# Main.net
KiCad netlist of a schematic drawn in Altium Designer
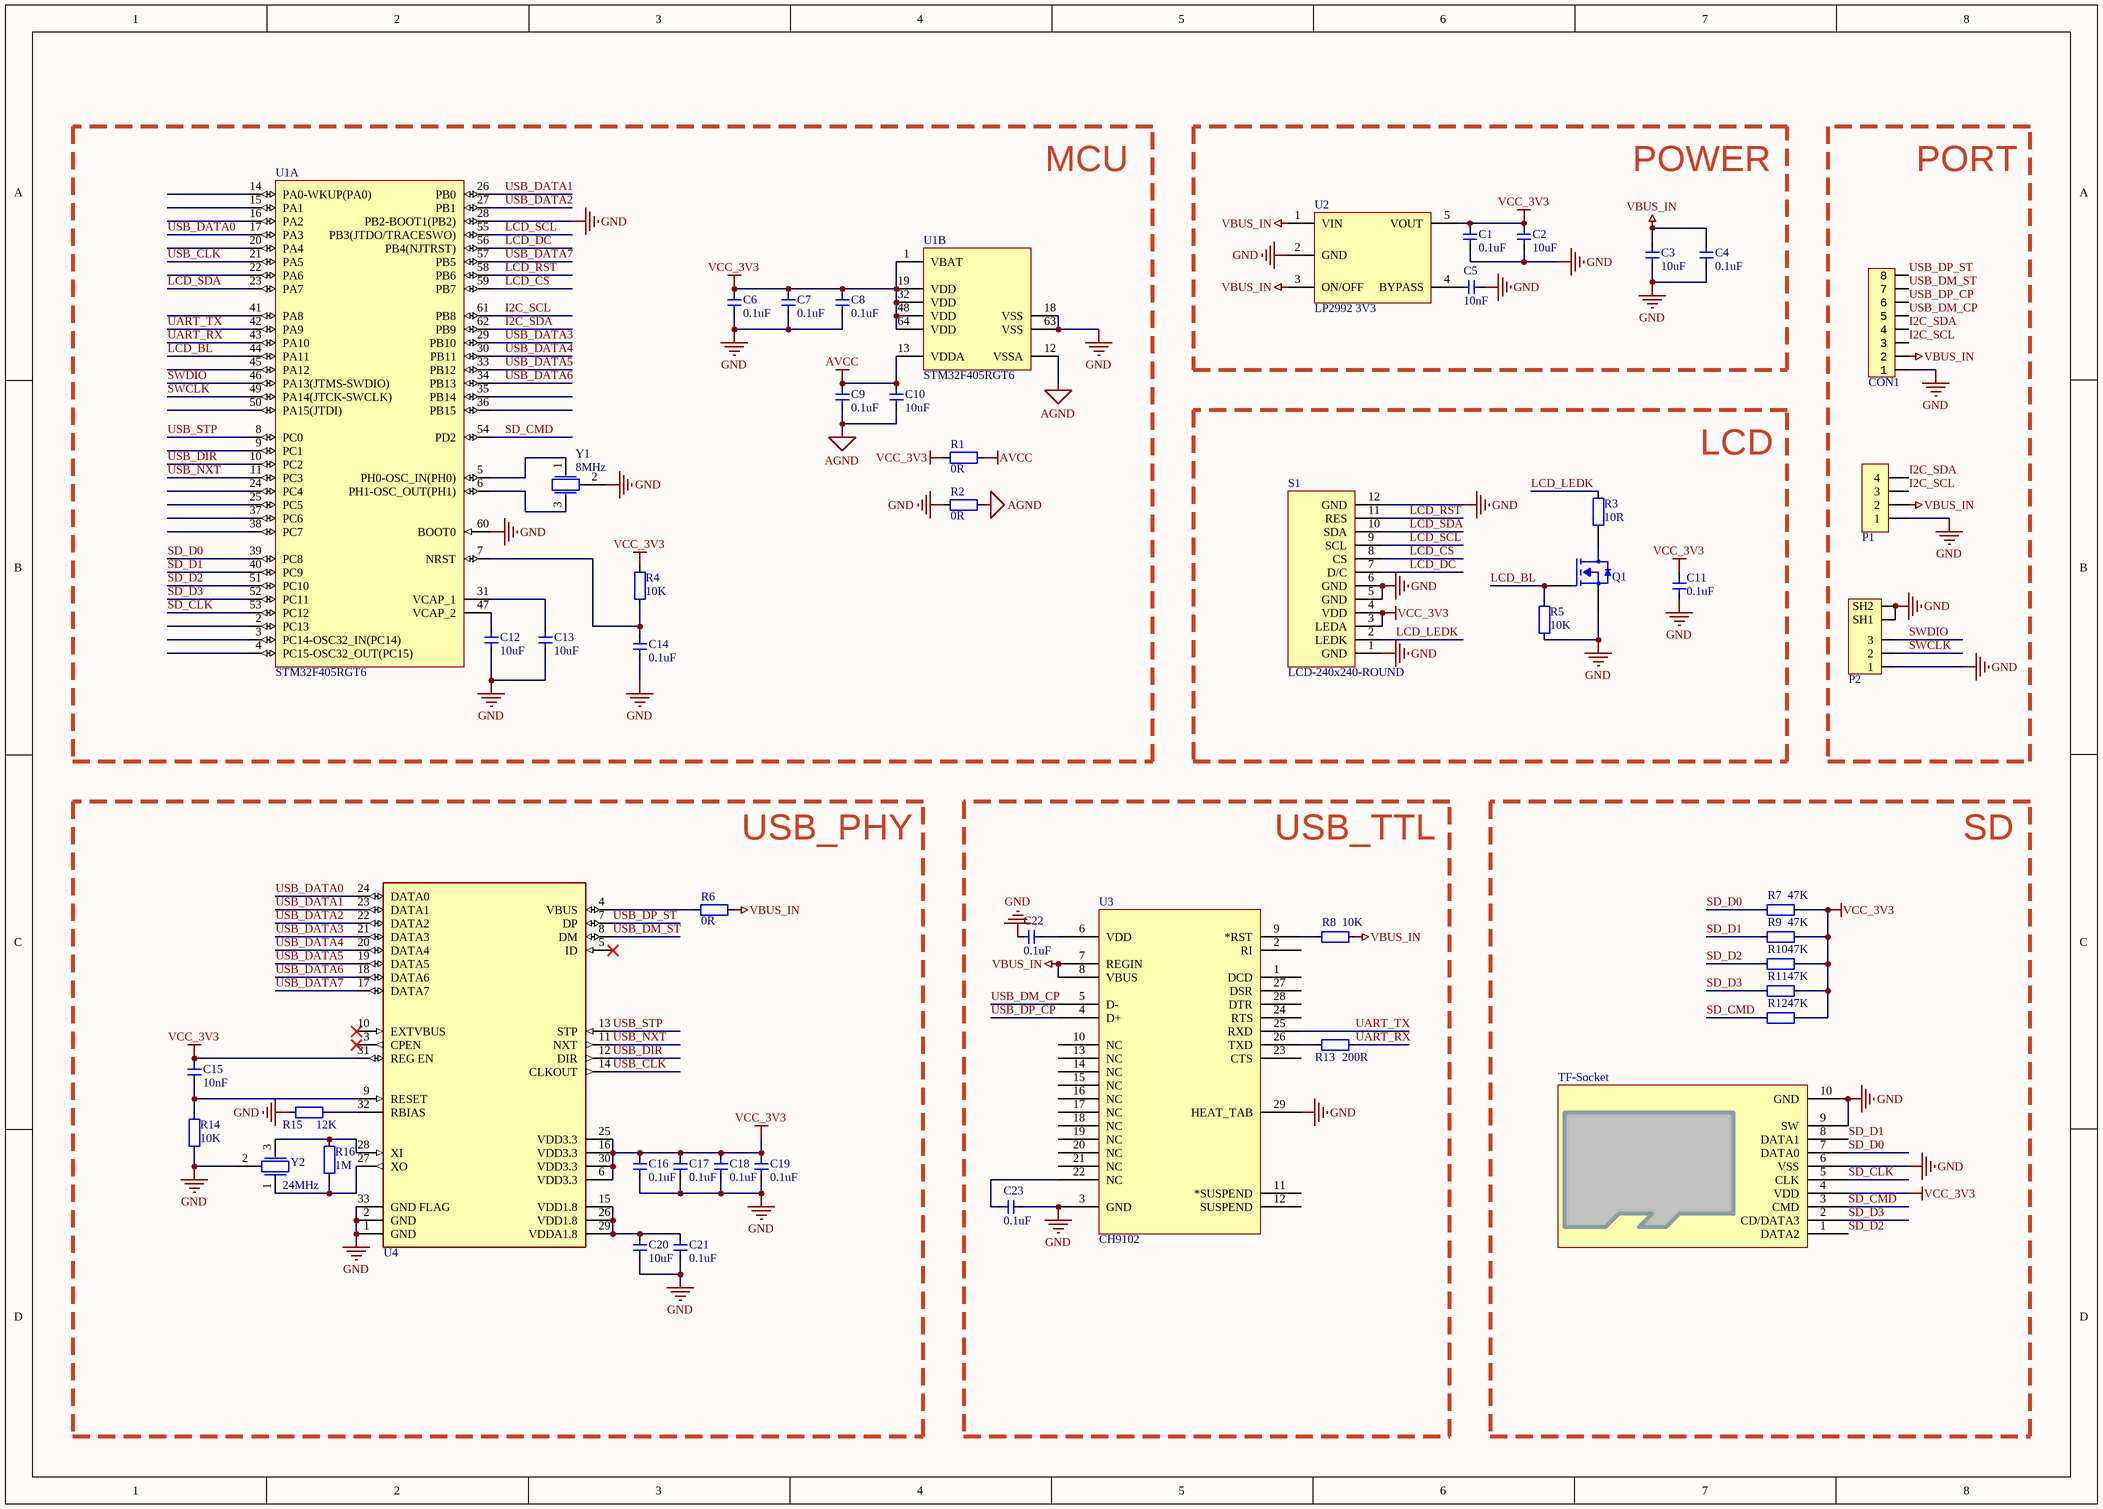
[diagram p0: Main.SchDoc]

(export (version "E")
  (design (tool "Eeschema 10.0.6"))
  (components
    (comp (ref "C1")
      (value "0.1uF")
      (footprint "ElectronBot:CAP_0402")
      (description "Capacitor")
      (libsource (lib "MyPcbLib") (part "电容-0402"))
    )
    (comp (ref "C2")
      (value "10uF")
      (footprint "ElectronBot:CAP_0402")
      (description "Capacitor")
      (libsource (lib "MyPcbLib") (part "电容-0402"))
    )
    (comp (ref "C3")
      (value "10uF")
      (footprint "ElectronBot:CAP_0402")
      (description "Capacitor")
      (libsource (lib "MyPcbLib") (part "电容-0402"))
    )
    (comp (ref "C4")
      (value "0.1uF")
      (footprint "ElectronBot:CAP_0402")
      (description "Capacitor")
      (libsource (lib "MyPcbLib") (part "电容-0402"))
    )
    (comp (ref "C5")
      (value "10nF")
      (footprint "ElectronBot:CAP_0402")
      (description "Capacitor")
      (libsource (lib "MyPcbLib") (part "电容-0402"))
    )
    (comp (ref "C6")
      (value "0.1uF")
      (footprint "ElectronBot:CAP_0402")
      (description "Capacitor")
      (libsource (lib "MyPcbLib") (part "电容-0402"))
    )
    (comp (ref "C7")
      (value "0.1uF")
      (footprint "ElectronBot:CAP_0402")
      (description "Capacitor")
      (libsource (lib "MyPcbLib") (part "电容-0402"))
    )
    (comp (ref "C8")
      (value "0.1uF")
      (footprint "ElectronBot:CAP_0402")
      (description "Capacitor")
      (libsource (lib "MyPcbLib") (part "电容-0402"))
    )
    (comp (ref "C9")
      (value "0.1uF")
      (footprint "ElectronBot:CAP_0402")
      (description "Capacitor")
      (libsource (lib "MyPcbLib") (part "电容-0402"))
    )
    (comp (ref "C10")
      (value "10uF")
      (footprint "ElectronBot:CAP_0402")
      (description "Capacitor")
      (libsource (lib "MyPcbLib") (part "电容-0402"))
    )
    (comp (ref "C11")
      (value "0.1uF")
      (footprint "ElectronBot:CAP_0402")
      (description "Capacitor")
      (libsource (lib "MyPcbLib") (part "电容-0402"))
    )
    (comp (ref "C12")
      (value "10uF")
      (footprint "ElectronBot:CAP_0402")
      (description "Capacitor")
      (libsource (lib "MyPcbLib") (part "电容-0402"))
    )
    (comp (ref "C13")
      (value "10uF")
      (footprint "ElectronBot:CAP_0402")
      (description "Capacitor")
      (libsource (lib "MyPcbLib") (part "电容-0402"))
    )
    (comp (ref "C14")
      (value "0.1uF")
      (footprint "ElectronBot:CAP_0402")
      (description "Capacitor")
      (libsource (lib "MyPcbLib") (part "电容-0402"))
    )
    (comp (ref "C15")
      (value "10nF")
      (footprint "ElectronBot:CAP_0402")
      (description "Capacitor")
      (libsource (lib "MyPcbLib") (part "电容-0402"))
    )
    (comp (ref "C16")
      (value "0.1uF")
      (footprint "ElectronBot:CAP_0402")
      (description "Capacitor")
      (libsource (lib "MyPcbLib") (part "电容-0402"))
    )
    (comp (ref "C17")
      (value "0.1uF")
      (footprint "ElectronBot:CAP_0402")
      (description "Capacitor")
      (libsource (lib "MyPcbLib") (part "电容-0402"))
    )
    (comp (ref "C18")
      (value "0.1uF")
      (footprint "ElectronBot:CAP_0402")
      (description "Capacitor")
      (libsource (lib "MyPcbLib") (part "电容-0402"))
    )
    (comp (ref "C19")
      (value "0.1uF")
      (footprint "ElectronBot:CAP_0402")
      (description "Capacitor")
      (libsource (lib "MyPcbLib") (part "电容-0402"))
    )
    (comp (ref "C20")
      (value "10uF")
      (footprint "ElectronBot:CAP_0402")
      (description "Capacitor")
      (libsource (lib "MyPcbLib") (part "电容-0402"))
    )
    (comp (ref "C21")
      (value "0.1uF")
      (footprint "ElectronBot:CAP_0402")
      (description "Capacitor")
      (libsource (lib "MyPcbLib") (part "电容-0402"))
    )
    (comp (ref "C22")
      (value "0.1uF")
      (footprint "ElectronBot:CAP_0402")
      (description "Capacitor")
      (libsource (lib "MyPcbLib") (part "电容-0402"))
    )
    (comp (ref "C23")
      (value "0.1uF")
      (footprint "ElectronBot:CAP_0402")
      (description "Capacitor")
      (libsource (lib "MyPcbLib") (part "电容-0402"))
    )
    (comp (ref "CON1")
      (value "FFC_0.5_8")
      (footprint "ElectronBot:FFC_0.5_8")
      (description "FFC")
      (libsource (lib "KitSprout") (part "FFC_0.5_8"))
    )
    (comp (ref "P1")
      (value "CON-4P")
      (footprint "ElectronBot:SH1.0-4P")
      (description "4P连接器")
      (libsource (lib "4.9 - 0.5mm连接器(FPC0.5)") (part "Header 4"))
    )
    (comp (ref "P2")
      (value "SH1.0-3P-STAND")
      (footprint "ElectronBot:SH1.0-3P-STAND")
      (description "Header")
      (libsource (lib "MyPcbLib") (part "SH1.0-3P-STAND"))
    )
    (comp (ref "Q1")
      (value "AO3400A")
      (footprint "ElectronBot:SOT23-3")
      (description "N-MOS")
      (libsource (lib "MyPcbLib") (part "AO3400A"))
    )
    (comp (ref "R1")
      (value "0R")
      (footprint "ElectronBot:RES_0402")
      (description "Resistor")
      (libsource (lib "") (part "电阻-0402_1"))
    )
    (comp (ref "R2")
      (value "0R")
      (footprint "ElectronBot:RES_0402")
      (description "Resistor")
      (libsource (lib "") (part "电阻-0402_1"))
    )
    (comp (ref "R3")
      (value "10R")
      (footprint "ElectronBot:RES_0402")
      (description "Resistor")
      (libsource (lib "MyPcbLib") (part "电阻-0402"))
    )
    (comp (ref "R4")
      (value "10K")
      (footprint "ElectronBot:RES_0402")
      (description "Resistor")
      (libsource (lib "MyPcbLib") (part "电阻-0402"))
    )
    (comp (ref "R5")
      (value "10K")
      (footprint "ElectronBot:RES_0402")
      (description "Resistor")
      (libsource (lib "MyPcbLib") (part "电阻-0402"))
    )
    (comp (ref "R6")
      (value "0R")
      (footprint "ElectronBot:RES_0402")
      (description "Resistor")
      (libsource (lib "") (part "电阻-0402_1"))
    )
    (comp (ref "R7")
      (value "47K")
      (footprint "ElectronBot:RES_0402")
      (description "Resistor")
      (libsource (lib "") (part "电阻-0402_1"))
    )
    (comp (ref "R8")
      (value "10K")
      (footprint "ElectronBot:RES_0402")
      (description "Resistor")
      (libsource (lib "") (part "电阻-0402_1"))
    )
    (comp (ref "R9")
      (value "47K")
      (footprint "ElectronBot:RES_0402")
      (description "Resistor")
      (libsource (lib "") (part "电阻-0402_1"))
    )
    (comp (ref "R10")
      (value "47K")
      (footprint "ElectronBot:RES_0402")
      (description "Resistor")
      (libsource (lib "") (part "电阻-0402_1"))
    )
    (comp (ref "R11")
      (value "47K")
      (footprint "ElectronBot:RES_0402")
      (description "Resistor")
      (libsource (lib "") (part "电阻-0402_1"))
    )
    (comp (ref "R12")
      (value "47K")
      (footprint "ElectronBot:RES_0402")
      (description "Resistor")
      (libsource (lib "") (part "电阻-0402_1"))
    )
    (comp (ref "R13")
      (value "200R")
      (footprint "ElectronBot:RES_0402")
      (description "Resistor")
      (libsource (lib "") (part "电阻-0402_1"))
    )
    (comp (ref "R14")
      (value "10K")
      (footprint "ElectronBot:RES_0402")
      (description "Resistor")
      (libsource (lib "") (part "电阻-0402_2"))
    )
    (comp (ref "R15")
      (value "12K")
      (footprint "ElectronBot:RES_0402")
      (description "Resistor")
      (libsource (lib "") (part "电阻-0402_1"))
    )
    (comp (ref "R16")
      (value "1M")
      (footprint "ElectronBot:RES_0402")
      (description "Resistor")
      (libsource (lib "") (part "电阻-0402_2"))
    )
    (comp (ref "S1")
      (value "LCD-240x240-ROUND")
      (footprint "ElectronBot:LCD-240x240-ROUND")
      (description "显示屏")
      (libsource (lib "mLib") (part "LCD-240x240-ROUND"))
    )
    (comp (ref "TF-Socket")
      (value "TF")
      (footprint "ElectronBot:TF-Card-Amphenol with TF")
      (description "8脚自弹")
      (libsource (lib "MyPcbLib") (part "TF卡座"))
    )
    (comp (ref "U1")
      (value "STM32F405RGT6")
      (footprint "ElectronBot:LQFP-64_N")
      (fields (field (name "MANUFACTURER") "STMicroelectronics"))
      (libsource (lib "STMicroelectronics STM32 F4") (part "STM32F405RGT6"))
    )
    (comp (ref "U2")
      (value "LP2992 3V3")
      (footprint "ElectronBot:SOT23-5")
      (description "LDO")
      (libsource (lib "MyPcbLib") (part "LP2992"))
    )
    (comp (ref "U3")
      (value "CH9102")
      (footprint "ElectronBot:QFN-28")
      (description "USB转TTL")
      (fields (field (name "PART NUMBER") "CP2102"))
      (libsource (lib "mLib") (part "CP2102"))
    )
    (comp (ref "U4")
      (value "USB3300-EZK-TR")
      (footprint "ElectronBot:QFN-32")
      (libsource (lib "mLib") (part "USB3300-EZK-TR"))
    )
    (comp (ref "Y1")
      (value "8MHz")
      (footprint "ElectronBot:晶振-3P")
      (description "村田贴片")
      (libsource (lib "MyPcbLib") (part "晶振-3Pin"))
    )
    (comp (ref "Y2")
      (value "24MHz")
      (footprint "ElectronBot:晶振-3P")
      (description "村田贴片")
      (libsource (lib "MyPcbLib") (part "晶振-3Pin"))
    )
  )
  (nets
    (net (code "1") (name "/I2C_SCL") (class "Default")
      (node (ref "CON1") (pin "3") (pinfunction "3_3") (pintype "passive"))
      (node (ref "P1") (pin "3") (pinfunction "3_3") (pintype "passive"))
      (node (ref "U1") (pin "61") (pinfunction "PB8_61") (pintype "bidirectional"))
    )
    (net (code "2") (name "/I2C_SDA") (class "Default")
      (node (ref "CON1") (pin "4") (pinfunction "4_4") (pintype "passive"))
      (node (ref "P1") (pin "4") (pinfunction "4_4") (pintype "passive"))
      (node (ref "U1") (pin "62") (pinfunction "PB9_62") (pintype "bidirectional"))
    )
    (net (code "3") (name "/LCD_BL") (class "Default")
      (node (ref "Q1") (pin "1") (pinfunction "G_1") (pintype "passive"))
      (node (ref "R5") (pin "2") (pinfunction "2_2") (pintype "passive"))
      (node (ref "U1") (pin "44") (pinfunction "PA11_44") (pintype "bidirectional"))
    )
    (net (code "4") (name "/LCD_CS") (class "Default")
      (node (ref "S1") (pin "8") (pinfunction "CS_8") (pintype "passive"))
      (node (ref "U1") (pin "59") (pinfunction "PB7_59") (pintype "bidirectional"))
    )
    (net (code "5") (name "/LCD_DC") (class "Default")
      (node (ref "S1") (pin "7") (pinfunction "D/C_7") (pintype "passive"))
      (node (ref "U1") (pin "56") (pinfunction "PB4(NJTRST)_56") (pintype "bidirectional"))
    )
    (net (code "6") (name "/LCD_LEDK") (class "Default")
      (node (ref "R3") (pin "2") (pinfunction "2_2") (pintype "passive"))
      (node (ref "S1") (pin "2") (pinfunction "LEDK_2") (pintype "passive"))
    )
    (net (code "7") (name "/LCD_RST") (class "Default")
      (node (ref "S1") (pin "11") (pinfunction "RES_11") (pintype "passive"))
      (node (ref "U1") (pin "58") (pinfunction "PB6_58") (pintype "bidirectional"))
    )
    (net (code "8") (name "/LCD_SCL") (class "Default")
      (node (ref "S1") (pin "9") (pinfunction "SCL_9") (pintype "passive"))
      (node (ref "U1") (pin "55") (pinfunction "PB3(JTDO/TRACESWO)_55") (pintype "bidirectional"))
    )
    (net (code "9") (name "/LCD_SDA") (class "Default")
      (node (ref "S1") (pin "10") (pinfunction "SDA_10") (pintype "passive"))
      (node (ref "U1") (pin "23") (pinfunction "PA7_23") (pintype "bidirectional"))
    )
    (net (code "10") (name "/SD_CLK") (class "Default")
      (node (ref "TF-Socket") (pin "5") (pinfunction "CLK_5") (pintype "passive"))
      (node (ref "U1") (pin "53") (pinfunction "PC12_53") (pintype "bidirectional"))
    )
    (net (code "11") (name "/SD_CMD") (class "Default")
      (node (ref "R12") (pin "2") (pinfunction "2_2") (pintype "passive"))
      (node (ref "TF-Socket") (pin "3") (pinfunction "CMD_3") (pintype "passive"))
      (node (ref "U1") (pin "54") (pinfunction "PD2_54") (pintype "bidirectional"))
    )
    (net (code "12") (name "/SD_D0") (class "Default")
      (node (ref "R7") (pin "2") (pinfunction "2_2") (pintype "passive"))
      (node (ref "TF-Socket") (pin "7") (pinfunction "DATA0_7") (pintype "passive"))
      (node (ref "U1") (pin "39") (pinfunction "PC8_39") (pintype "bidirectional"))
    )
    (net (code "13") (name "/SD_D1") (class "Default")
      (node (ref "R9") (pin "2") (pinfunction "2_2") (pintype "passive"))
      (node (ref "TF-Socket") (pin "8") (pinfunction "DATA1_8") (pintype "passive"))
      (node (ref "U1") (pin "40") (pinfunction "PC9_40") (pintype "bidirectional"))
    )
    (net (code "14") (name "/SD_D2") (class "Default")
      (node (ref "R10") (pin "2") (pinfunction "2_2") (pintype "passive"))
      (node (ref "TF-Socket") (pin "1") (pinfunction "DATA2_1") (pintype "passive"))
      (node (ref "U1") (pin "51") (pinfunction "PC10_51") (pintype "bidirectional"))
    )
    (net (code "15") (name "/SD_D3") (class "Default")
      (node (ref "R11") (pin "2") (pinfunction "2_2") (pintype "passive"))
      (node (ref "TF-Socket") (pin "2") (pinfunction "CD/DATA3_2") (pintype "passive"))
      (node (ref "U1") (pin "52") (pinfunction "PC11_52") (pintype "bidirectional"))
    )
    (net (code "16") (name "/SWCLK") (class "Default")
      (node (ref "P2") (pin "2") (pinfunction "2_2") (pintype "passive"))
      (node (ref "U1") (pin "49") (pinfunction "PA14(JTCK-SWCLK)_49") (pintype "bidirectional"))
    )
    (net (code "17") (name "/SWDIO") (class "Default")
      (node (ref "P2") (pin "3") (pinfunction "3_3") (pintype "passive"))
      (node (ref "U1") (pin "46") (pinfunction "PA13(JTMS-SWDIO)_46") (pintype "bidirectional"))
    )
    (net (code "18") (name "/UART_RX") (class "Default")
      (node (ref "R13") (pin "1") (pinfunction "1_1") (pintype "passive"))
      (node (ref "U1") (pin "43") (pinfunction "PA10_43") (pintype "bidirectional"))
    )
    (net (code "19") (name "/UART_TX") (class "Default")
      (node (ref "U1") (pin "42") (pinfunction "PA9_42") (pintype "bidirectional"))
      (node (ref "U3") (pin "25") (pinfunction "RXD_25") (pintype "passive"))
    )
    (net (code "20") (name "/USB_CLK") (class "Default")
      (node (ref "U1") (pin "21") (pinfunction "PA5_21") (pintype "bidirectional"))
      (node (ref "U4") (pin "14") (pinfunction "CLKOUT_14") (pintype "output"))
    )
    (net (code "21") (name "/USB_DATA0") (class "Default")
      (node (ref "U1") (pin "17") (pinfunction "PA3_17") (pintype "bidirectional"))
      (node (ref "U4") (pin "24") (pinfunction "DATA0_24") (pintype "bidirectional"))
    )
    (net (code "22") (name "/USB_DATA1") (class "Default")
      (node (ref "U1") (pin "26") (pinfunction "PB0_26") (pintype "bidirectional"))
      (node (ref "U4") (pin "23") (pinfunction "DATA1_23") (pintype "bidirectional"))
    )
    (net (code "23") (name "/USB_DATA2") (class "Default")
      (node (ref "U1") (pin "27") (pinfunction "PB1_27") (pintype "bidirectional"))
      (node (ref "U4") (pin "22") (pinfunction "DATA2_22") (pintype "bidirectional"))
    )
    (net (code "24") (name "/USB_DATA3") (class "Default")
      (node (ref "U1") (pin "29") (pinfunction "PB10_29") (pintype "bidirectional"))
      (node (ref "U4") (pin "21") (pinfunction "DATA3_21") (pintype "bidirectional"))
    )
    (net (code "25") (name "/USB_DATA4") (class "Default")
      (node (ref "U1") (pin "30") (pinfunction "PB11_30") (pintype "bidirectional"))
      (node (ref "U4") (pin "20") (pinfunction "DATA4_20") (pintype "bidirectional"))
    )
    (net (code "26") (name "/USB_DATA5") (class "Default")
      (node (ref "U1") (pin "33") (pinfunction "PB12_33") (pintype "bidirectional"))
      (node (ref "U4") (pin "19") (pinfunction "DATA5_19") (pintype "bidirectional"))
    )
    (net (code "27") (name "/USB_DATA6") (class "Default")
      (node (ref "U1") (pin "34") (pinfunction "PB13_34") (pintype "bidirectional"))
      (node (ref "U4") (pin "18") (pinfunction "DATA6_18") (pintype "bidirectional"))
    )
    (net (code "28") (name "/USB_DATA7") (class "Default")
      (node (ref "U1") (pin "57") (pinfunction "PB5_57") (pintype "bidirectional"))
      (node (ref "U4") (pin "17") (pinfunction "DATA7_17") (pintype "bidirectional"))
    )
    (net (code "29") (name "/USB_DIR") (class "Default")
      (node (ref "U1") (pin "10") (pinfunction "PC2_10") (pintype "bidirectional"))
      (node (ref "U4") (pin "12") (pinfunction "DIR_12") (pintype "output"))
    )
    (net (code "30") (name "/USB_DM_CP") (class "Default")
      (node (ref "CON1") (pin "5") (pinfunction "5_5") (pintype "passive"))
      (node (ref "U3") (pin "5") (pinfunction "D-_5") (pintype "passive"))
    )
    (net (code "31") (name "/USB_DM_ST") (class "Default")
      (node (ref "CON1") (pin "7") (pinfunction "7_7") (pintype "passive"))
      (node (ref "U4") (pin "8") (pinfunction "DM_8") (pintype "bidirectional"))
    )
    (net (code "32") (name "/USB_DP_CP") (class "Default")
      (node (ref "CON1") (pin "6") (pinfunction "6_6") (pintype "passive"))
      (node (ref "U3") (pin "4") (pinfunction "D+_4") (pintype "passive"))
    )
    (net (code "33") (name "/USB_DP_ST") (class "Default")
      (node (ref "CON1") (pin "8") (pinfunction "8_8") (pintype "passive"))
      (node (ref "U4") (pin "7") (pinfunction "DP_7") (pintype "bidirectional"))
    )
    (net (code "34") (name "/USB_NXT") (class "Default")
      (node (ref "U1") (pin "11") (pinfunction "PC3_11") (pintype "bidirectional"))
      (node (ref "U4") (pin "11") (pinfunction "NXT_11") (pintype "output"))
    )
    (net (code "35") (name "/USB_STP") (class "Default")
      (node (ref "U1") (pin "8") (pinfunction "PC0_8") (pintype "bidirectional"))
      (node (ref "U4") (pin "13") (pinfunction "STP_13") (pintype "input"))
    )
    (net (code "36") (name "AGND") (class "Default")
      (node (ref "C10") (pin "1") (pinfunction "1_1") (pintype "passive"))
      (node (ref "C9") (pin "1") (pinfunction "1_1") (pintype "passive"))
      (node (ref "R2") (pin "1") (pinfunction "1_1") (pintype "passive"))
      (node (ref "U1") (pin "12") (pinfunction "VSSA_12") (pintype "power_in"))
    )
    (net (code "37") (name "AVCC") (class "Default")
      (node (ref "C10") (pin "2") (pinfunction "2_2") (pintype "passive"))
      (node (ref "C9") (pin "2") (pinfunction "2_2") (pintype "passive"))
      (node (ref "R1") (pin "1") (pinfunction "1_1") (pintype "passive"))
      (node (ref "U1") (pin "13") (pinfunction "VDDA_13") (pintype "power_in"))
    )
    (net (code "38") (name "GND") (class "Default")
      (node (ref "C1") (pin "1") (pinfunction "1_1") (pintype "passive"))
      (node (ref "C11") (pin "1") (pinfunction "1_1") (pintype "passive"))
      (node (ref "C12") (pin "1") (pinfunction "1_1") (pintype "passive"))
      (node (ref "C13") (pin "1") (pinfunction "1_1") (pintype "passive"))
      (node (ref "C14") (pin "1") (pinfunction "1_1") (pintype "passive"))
      (node (ref "C16") (pin "2") (pinfunction "2_2") (pintype "passive"))
      (node (ref "C17") (pin "2") (pinfunction "2_2") (pintype "passive"))
      (node (ref "C18") (pin "2") (pinfunction "2_2") (pintype "passive"))
      (node (ref "C19") (pin "2") (pinfunction "2_2") (pintype "passive"))
      (node (ref "C2") (pin "1") (pinfunction "1_1") (pintype "passive"))
      (node (ref "C20") (pin "2") (pinfunction "2_2") (pintype "passive"))
      (node (ref "C21") (pin "2") (pinfunction "2_2") (pintype "passive"))
      (node (ref "C22") (pin "2") (pinfunction "2_2") (pintype "passive"))
      (node (ref "C23") (pin "1") (pinfunction "1_1") (pintype "passive"))
      (node (ref "C3") (pin "1") (pinfunction "1_1") (pintype "passive"))
      (node (ref "C4") (pin "1") (pinfunction "1_1") (pintype "passive"))
      (node (ref "C5") (pin "1") (pinfunction "1_1") (pintype "passive"))
      (node (ref "C6") (pin "1") (pinfunction "1_1") (pintype "passive"))
      (node (ref "C7") (pin "1") (pinfunction "1_1") (pintype "passive"))
      (node (ref "C8") (pin "1") (pinfunction "1_1") (pintype "passive"))
      (node (ref "CON1") (pin "1") (pinfunction "1_1") (pintype "passive"))
      (node (ref "P1") (pin "1") (pinfunction "1_1") (pintype "passive"))
      (node (ref "P2") (pin "1") (pinfunction "1_1") (pintype "passive"))
      (node (ref "P2") (pin "SH1") (pinfunction "SH1_SH1") (pintype "passive"))
      (node (ref "P2") (pin "SH2") (pinfunction "SH2_SH2") (pintype "passive"))
      (node (ref "Q1") (pin "2") (pinfunction "S_2") (pintype "passive"))
      (node (ref "R14") (pin "2") (pinfunction "2_2") (pintype "passive"))
      (node (ref "R15") (pin "2") (pinfunction "2_2") (pintype "passive"))
      (node (ref "R2") (pin "2") (pinfunction "2_2") (pintype "passive"))
      (node (ref "R5") (pin "1") (pinfunction "1_1") (pintype "passive"))
      (node (ref "S1") (pin "1") (pinfunction "GND_1") (pintype "passive"))
      (node (ref "S1") (pin "12") (pinfunction "GND_12") (pintype "passive"))
      (node (ref "S1") (pin "5") (pinfunction "GND_5") (pintype "passive"))
      (node (ref "S1") (pin "6") (pinfunction "GND_6") (pintype "passive"))
      (node (ref "TF-Socket") (pin "10") (pinfunction "GND_10") (pintype "passive"))
      (node (ref "TF-Socket") (pin "6") (pinfunction "VSS_6") (pintype "passive"))
      (node (ref "TF-Socket") (pin "9") (pinfunction "SW_9") (pintype "passive"))
      (node (ref "U1") (pin "18") (pinfunction "VSS_18") (pintype "power_in"))
      (node (ref "U1") (pin "28") (pinfunction "PB2-BOOT1(PB2)_28") (pintype "bidirectional"))
      (node (ref "U1") (pin "60") (pinfunction "BOOT0_60") (pintype "input"))
      (node (ref "U1") (pin "63") (pinfunction "VSS_63") (pintype "power_in"))
      (node (ref "U2") (pin "2") (pinfunction "GND_2") (pintype "passive"))
      (node (ref "U3") (pin "29") (pinfunction "HEAT_TAB_29") (pintype "passive"))
      (node (ref "U3") (pin "3") (pinfunction "GND_3") (pintype "passive"))
      (node (ref "U4") (pin "1") (pinfunction "GND_1") (pintype "power_in"))
      (node (ref "U4") (pin "2") (pinfunction "GND_2") (pintype "power_in"))
      (node (ref "U4") (pin "33") (pinfunction "GND_FLAG_33") (pintype "power_in"))
      (node (ref "Y1") (pin "2") (pinfunction "2_2") (pintype "passive"))
      (node (ref "Y2") (pin "2") (pinfunction "2_2") (pintype "passive"))
    )
    (net (code "39") (name "Net-(C23-Pad2)") (class "Default")
      (node (ref "C23") (pin "2") (pinfunction "2_2") (pintype "passive"))
      (node (ref "U3") (pin "22") (pinfunction "NC_22") (pintype "passive"))
    )
    (net (code "40") (name "Net-(Q1-D)") (class "Default")
      (node (ref "Q1") (pin "3") (pinfunction "D_3") (pintype "passive"))
      (node (ref "R3") (pin "1") (pinfunction "1_1") (pintype "passive"))
    )
    (net (code "41") (name "Net-(U1A-NRST)") (class "Default")
      (node (ref "C14") (pin "2") (pinfunction "2_2") (pintype "passive"))
      (node (ref "R4") (pin "1") (pinfunction "1_1") (pintype "passive"))
      (node (ref "U1") (pin "7") (pinfunction "NRST_7") (pintype "bidirectional"))
    )
    (net (code "42") (name "Net-(U1A-PH0-OSC_IN(PH0))") (class "Default")
      (node (ref "U1") (pin "5") (pinfunction "PH0-OSC_IN(PH0)_5") (pintype "bidirectional"))
      (node (ref "Y1") (pin "1") (pinfunction "1_1") (pintype "passive"))
    )
    (net (code "43") (name "Net-(U1A-PH1-OSC_OUT(PH1))") (class "Default")
      (node (ref "U1") (pin "6") (pinfunction "PH1-OSC_OUT(PH1)_6") (pintype "bidirectional"))
      (node (ref "Y1") (pin "3") (pinfunction "3_3") (pintype "passive"))
    )
    (net (code "44") (name "Net-(U1A-VCAP_1)") (class "Default")
      (node (ref "C13") (pin "2") (pinfunction "2_2") (pintype "passive"))
      (node (ref "U1") (pin "31") (pinfunction "VCAP_1_31") (pintype "power_in"))
    )
    (net (code "45") (name "Net-(U1A-VCAP_2)") (class "Default")
      (node (ref "C12") (pin "2") (pinfunction "2_2") (pintype "passive"))
      (node (ref "U1") (pin "47") (pinfunction "VCAP_2_47") (pintype "power_in"))
    )
    (net (code "46") (name "Net-(U2-BYPASS)") (class "Default")
      (node (ref "C5") (pin "2") (pinfunction "2_2") (pintype "passive"))
      (node (ref "U2") (pin "4") (pinfunction "BYPASS_4") (pintype "passive"))
    )
    (net (code "47") (name "Net-(U3-*RST)") (class "Default")
      (node (ref "R8") (pin "2") (pinfunction "2_2") (pintype "passive"))
      (node (ref "U3") (pin "9") (pinfunction "*RST_9") (pintype "passive"))
    )
    (net (code "48") (name "Net-(U3-TXD)") (class "Default")
      (node (ref "R13") (pin "2") (pinfunction "2_2") (pintype "passive"))
      (node (ref "U3") (pin "26") (pinfunction "TXD_26") (pintype "passive"))
    )
    (net (code "49") (name "Net-(U3-VDD)") (class "Default")
      (node (ref "C22") (pin "1") (pinfunction "1_1") (pintype "passive"))
      (node (ref "U3") (pin "6") (pinfunction "VDD_6") (pintype "passive"))
    )
    (net (code "50") (name "Net-(U4-RBIAS)") (class "Default")
      (node (ref "R15") (pin "1") (pinfunction "1_1") (pintype "passive"))
      (node (ref "U4") (pin "32") (pinfunction "RBIAS_32") (pintype "power_in"))
    )
    (net (code "51") (name "Net-(U4-RESET)") (class "Default")
      (node (ref "C15") (pin "2") (pinfunction "2_2") (pintype "passive"))
      (node (ref "R14") (pin "1") (pinfunction "1_1") (pintype "passive"))
      (node (ref "U4") (pin "9") (pinfunction "RESET_9") (pintype "input"))
    )
    (net (code "52") (name "Net-(U4-VBUS)") (class "Default")
      (node (ref "R6") (pin "2") (pinfunction "2_2") (pintype "passive"))
      (node (ref "U4") (pin "4") (pinfunction "VBUS_4") (pintype "bidirectional"))
    )
    (net (code "53") (name "Net-(U4-VDDA1.8)") (class "Default")
      (node (ref "C20") (pin "1") (pinfunction "1_1") (pintype "passive"))
      (node (ref "C21") (pin "1") (pinfunction "1_1") (pintype "passive"))
      (node (ref "U4") (pin "15") (pinfunction "VDD1.8_15") (pintype "power_in"))
      (node (ref "U4") (pin "26") (pinfunction "VDD1.8_26") (pintype "power_in"))
      (node (ref "U4") (pin "29") (pinfunction "VDDA1.8_29") (pintype "power_in"))
    )
    (net (code "54") (name "Net-(U4-XI)") (class "Default")
      (node (ref "R16") (pin "1") (pinfunction "1_1") (pintype "passive"))
      (node (ref "U4") (pin "28") (pinfunction "XI_28") (pintype "input"))
      (node (ref "Y2") (pin "3") (pinfunction "3_3") (pintype "passive"))
    )
    (net (code "55") (name "Net-(U4-XO)") (class "Default")
      (node (ref "R16") (pin "2") (pinfunction "2_2") (pintype "passive"))
      (node (ref "U4") (pin "27") (pinfunction "XO_27") (pintype "output"))
      (node (ref "Y2") (pin "1") (pinfunction "1_1") (pintype "passive"))
    )
    (net (code "56") (name "VBUS_IN") (class "Default")
      (node (ref "C3") (pin "2") (pinfunction "2_2") (pintype "passive"))
      (node (ref "C4") (pin "2") (pinfunction "2_2") (pintype "passive"))
      (node (ref "CON1") (pin "2") (pinfunction "2_2") (pintype "passive"))
      (node (ref "P1") (pin "2") (pinfunction "2_2") (pintype "passive"))
      (node (ref "R6") (pin "1") (pinfunction "1_1") (pintype "passive"))
      (node (ref "R8") (pin "1") (pinfunction "1_1") (pintype "passive"))
      (node (ref "U2") (pin "1") (pinfunction "VIN_1") (pintype "passive"))
      (node (ref "U2") (pin "3") (pinfunction "ON/OFF_3") (pintype "passive"))
      (node (ref "U3") (pin "7") (pinfunction "REGIN_7") (pintype "passive"))
      (node (ref "U3") (pin "8") (pinfunction "VBUS_8") (pintype "passive"))
    )
    (net (code "57") (name "VCC_3V3") (class "Default")
      (node (ref "C1") (pin "2") (pinfunction "2_2") (pintype "passive"))
      (node (ref "C11") (pin "2") (pinfunction "2_2") (pintype "passive"))
      (node (ref "C15") (pin "1") (pinfunction "1_1") (pintype "passive"))
      (node (ref "C16") (pin "1") (pinfunction "1_1") (pintype "passive"))
      (node (ref "C17") (pin "1") (pinfunction "1_1") (pintype "passive"))
      (node (ref "C18") (pin "1") (pinfunction "1_1") (pintype "passive"))
      (node (ref "C19") (pin "1") (pinfunction "1_1") (pintype "passive"))
      (node (ref "C2") (pin "2") (pinfunction "2_2") (pintype "passive"))
      (node (ref "C6") (pin "2") (pinfunction "2_2") (pintype "passive"))
      (node (ref "C7") (pin "2") (pinfunction "2_2") (pintype "passive"))
      (node (ref "C8") (pin "2") (pinfunction "2_2") (pintype "passive"))
      (node (ref "R1") (pin "2") (pinfunction "2_2") (pintype "passive"))
      (node (ref "R10") (pin "1") (pinfunction "1_1") (pintype "passive"))
      (node (ref "R11") (pin "1") (pinfunction "1_1") (pintype "passive"))
      (node (ref "R12") (pin "1") (pinfunction "1_1") (pintype "passive"))
      (node (ref "R4") (pin "2") (pinfunction "2_2") (pintype "passive"))
      (node (ref "R7") (pin "1") (pinfunction "1_1") (pintype "passive"))
      (node (ref "R9") (pin "1") (pinfunction "1_1") (pintype "passive"))
      (node (ref "S1") (pin "3") (pinfunction "LEDA_3") (pintype "passive"))
      (node (ref "S1") (pin "4") (pinfunction "VDD_4") (pintype "passive"))
      (node (ref "TF-Socket") (pin "4") (pinfunction "VDD_4") (pintype "passive"))
      (node (ref "U1") (pin "1") (pinfunction "VBAT_1") (pintype "power_in"))
      (node (ref "U1") (pin "19") (pinfunction "VDD_19") (pintype "power_in"))
      (node (ref "U1") (pin "32") (pinfunction "VDD_32") (pintype "power_in"))
      (node (ref "U1") (pin "48") (pinfunction "VDD_48") (pintype "power_in"))
      (node (ref "U1") (pin "64") (pinfunction "VDD_64") (pintype "power_in"))
      (node (ref "U2") (pin "5") (pinfunction "VOUT_5") (pintype "passive"))
      (node (ref "U4") (pin "16") (pinfunction "VDD3.3_16") (pintype "power_in"))
      (node (ref "U4") (pin "25") (pinfunction "VDD3.3_25") (pintype "power_in"))
      (node (ref "U4") (pin "30") (pinfunction "VDD3.3_30") (pintype "power_in"))
      (node (ref "U4") (pin "31") (pinfunction "REG_EN_31") (pintype "bidirectional"))
      (node (ref "U4") (pin "6") (pinfunction "VDD3.3_6") (pintype "power_in"))
    )
    (net (code "58") (name "unconnected-(U1A-PA0-WKUP(PA0)-Pad14)") (class "Default")
      (node (ref "U1") (pin "14") (pinfunction "PA0-WKUP(PA0)_14") (pintype "bidirectional"))
    )
    (net (code "59") (name "unconnected-(U1A-PA1-Pad15)") (class "Default")
      (node (ref "U1") (pin "15") (pinfunction "PA1_15") (pintype "bidirectional"))
    )
    (net (code "60") (name "unconnected-(U1A-PA2-Pad16)") (class "Default")
      (node (ref "U1") (pin "16") (pinfunction "PA2_16") (pintype "bidirectional"))
    )
    (net (code "61") (name "unconnected-(U1A-PA4-Pad20)") (class "Default")
      (node (ref "U1") (pin "20") (pinfunction "PA4_20") (pintype "bidirectional"))
    )
    (net (code "62") (name "unconnected-(U1A-PA6-Pad22)") (class "Default")
      (node (ref "U1") (pin "22") (pinfunction "PA6_22") (pintype "bidirectional"))
    )
    (net (code "63") (name "unconnected-(U1A-PA8-Pad41)") (class "Default")
      (node (ref "U1") (pin "41") (pinfunction "PA8_41") (pintype "bidirectional"))
    )
    (net (code "64") (name "unconnected-(U1A-PA12-Pad45)") (class "Default")
      (node (ref "U1") (pin "45") (pinfunction "PA12_45") (pintype "bidirectional"))
    )
    (net (code "65") (name "unconnected-(U1A-PA15(JTDI)-Pad50)") (class "Default")
      (node (ref "U1") (pin "50") (pinfunction "PA15(JTDI)_50") (pintype "bidirectional"))
    )
    (net (code "66") (name "unconnected-(U1A-PB14-Pad35)") (class "Default")
      (node (ref "U1") (pin "35") (pinfunction "PB14_35") (pintype "bidirectional"))
    )
    (net (code "67") (name "unconnected-(U1A-PB15-Pad36)") (class "Default")
      (node (ref "U1") (pin "36") (pinfunction "PB15_36") (pintype "bidirectional"))
    )
    (net (code "68") (name "unconnected-(U1A-PC1-Pad9)") (class "Default")
      (node (ref "U1") (pin "9") (pinfunction "PC1_9") (pintype "bidirectional"))
    )
    (net (code "69") (name "unconnected-(U1A-PC4-Pad24)") (class "Default")
      (node (ref "U1") (pin "24") (pinfunction "PC4_24") (pintype "bidirectional"))
    )
    (net (code "70") (name "unconnected-(U1A-PC5-Pad25)") (class "Default")
      (node (ref "U1") (pin "25") (pinfunction "PC5_25") (pintype "bidirectional"))
    )
    (net (code "71") (name "unconnected-(U1A-PC6-Pad37)") (class "Default")
      (node (ref "U1") (pin "37") (pinfunction "PC6_37") (pintype "bidirectional"))
    )
    (net (code "72") (name "unconnected-(U1A-PC7-Pad38)") (class "Default")
      (node (ref "U1") (pin "38") (pinfunction "PC7_38") (pintype "bidirectional"))
    )
    (net (code "73") (name "unconnected-(U1A-PC13-Pad2)") (class "Default")
      (node (ref "U1") (pin "2") (pinfunction "PC13_2") (pintype "bidirectional"))
    )
    (net (code "74") (name "unconnected-(U1A-PC14-OSC32_IN(PC14)-Pad3)") (class "Default")
      (node (ref "U1") (pin "3") (pinfunction "PC14-OSC32_IN(PC14)_3") (pintype "bidirectional"))
    )
    (net (code "75") (name "unconnected-(U1A-PC15-OSC32_OUT(PC15)-Pad4)") (class "Default")
      (node (ref "U1") (pin "4") (pinfunction "PC15-OSC32_OUT(PC15)_4") (pintype "bidirectional"))
    )
    (net (code "76") (name "unconnected-(U3-*SUSPEND-Pad11)") (class "Default")
      (node (ref "U3") (pin "11") (pinfunction "*SUSPEND_11") (pintype "passive"))
    )
    (net (code "77") (name "unconnected-(U3-CTS-Pad23)") (class "Default")
      (node (ref "U3") (pin "23") (pinfunction "CTS_23") (pintype "passive"))
    )
    (net (code "78") (name "unconnected-(U3-DCD-Pad1)") (class "Default")
      (node (ref "U3") (pin "1") (pinfunction "DCD_1") (pintype "passive"))
    )
    (net (code "79") (name "unconnected-(U3-DSR-Pad27)") (class "Default")
      (node (ref "U3") (pin "27") (pinfunction "DSR_27") (pintype "passive"))
    )
    (net (code "80") (name "unconnected-(U3-DTR-Pad28)") (class "Default")
      (node (ref "U3") (pin "28") (pinfunction "DTR_28") (pintype "passive"))
    )
    (net (code "81") (name "unconnected-(U3-NC-Pad10)") (class "Default")
      (node (ref "U3") (pin "10") (pinfunction "NC_10") (pintype "passive"))
    )
    (net (code "82") (name "unconnected-(U3-NC-Pad13)") (class "Default")
      (node (ref "U3") (pin "13") (pinfunction "NC_13") (pintype "passive"))
    )
    (net (code "83") (name "unconnected-(U3-NC-Pad14)") (class "Default")
      (node (ref "U3") (pin "14") (pinfunction "NC_14") (pintype "passive"))
    )
    (net (code "84") (name "unconnected-(U3-NC-Pad15)") (class "Default")
      (node (ref "U3") (pin "15") (pinfunction "NC_15") (pintype "passive"))
    )
    (net (code "85") (name "unconnected-(U3-NC-Pad16)") (class "Default")
      (node (ref "U3") (pin "16") (pinfunction "NC_16") (pintype "passive"))
    )
    (net (code "86") (name "unconnected-(U3-NC-Pad17)") (class "Default")
      (node (ref "U3") (pin "17") (pinfunction "NC_17") (pintype "passive"))
    )
    (net (code "87") (name "unconnected-(U3-NC-Pad18)") (class "Default")
      (node (ref "U3") (pin "18") (pinfunction "NC_18") (pintype "passive"))
    )
    (net (code "88") (name "unconnected-(U3-NC-Pad19)") (class "Default")
      (node (ref "U3") (pin "19") (pinfunction "NC_19") (pintype "passive"))
    )
    (net (code "89") (name "unconnected-(U3-NC-Pad20)") (class "Default")
      (node (ref "U3") (pin "20") (pinfunction "NC_20") (pintype "passive"))
    )
    (net (code "90") (name "unconnected-(U3-NC-Pad21)") (class "Default")
      (node (ref "U3") (pin "21") (pinfunction "NC_21") (pintype "passive"))
    )
    (net (code "91") (name "unconnected-(U3-RI-Pad2)") (class "Default")
      (node (ref "U3") (pin "2") (pinfunction "RI_2") (pintype "passive"))
    )
    (net (code "92") (name "unconnected-(U3-RTS-Pad24)") (class "Default")
      (node (ref "U3") (pin "24") (pinfunction "RTS_24") (pintype "passive"))
    )
    (net (code "93") (name "unconnected-(U3-SUSPEND-Pad12)") (class "Default")
      (node (ref "U3") (pin "12") (pinfunction "SUSPEND_12") (pintype "passive"))
    )
    (net (code "94") (name "unconnected-(U4-CPEN-Pad3)") (class "Default")
      (node (ref "U4") (pin "3") (pinfunction "CPEN_3") (pintype "output+no_connect"))
    )
    (net (code "95") (name "unconnected-(U4-EXTVBUS-Pad10)") (class "Default")
      (node (ref "U4") (pin "10") (pinfunction "EXTVBUS_10") (pintype "input+no_connect"))
    )
    (net (code "96") (name "unconnected-(U4-ID-Pad5)") (class "Default")
      (node (ref "U4") (pin "5") (pinfunction "ID_5") (pintype "input+no_connect"))
    )
  )
)
